# Faders.net
KiCad netlist of a schematic drawn in EAGLE
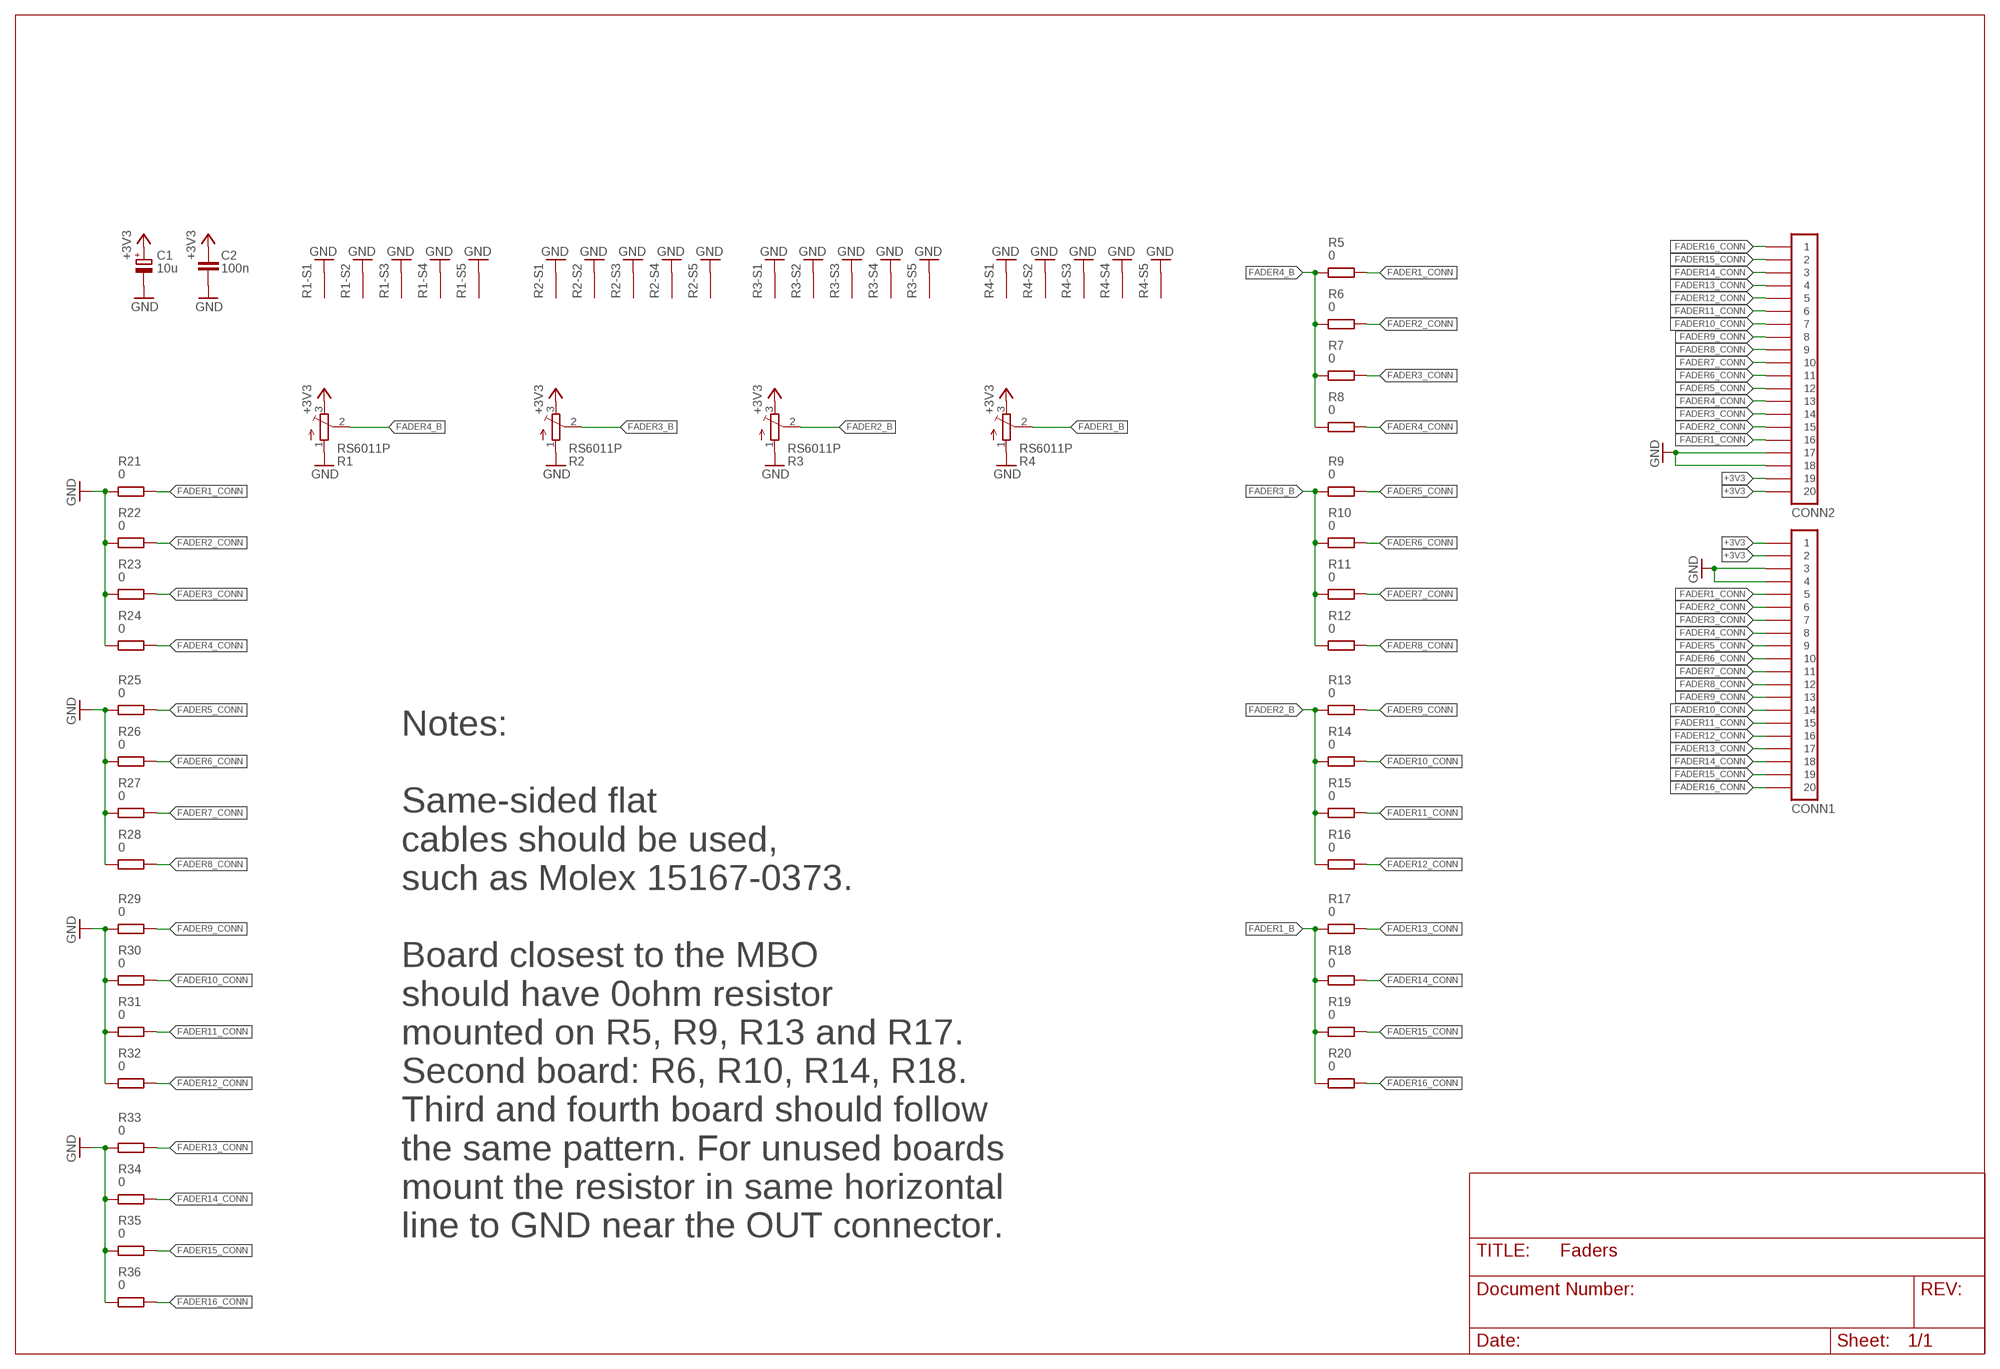
[diagram p0: schematic, sheet 1]

(export (version "E")
  (design (tool "Eeschema 10.0.6"))
  (components
    (comp (ref "C1")
      (value "10u")
      (footprint "eagle-import:C-TH-E-0401")
      (libsource (lib "eagle-import") (part "ELECTROLYTIC_CAPACITOR-C-TH-E-0401"))
    )
    (comp (ref "C2")
      (value "100n")
      (footprint "eagle-import:C0805")
      (libsource (lib "eagle-import") (part "CAPACITOR-0805"))
    )
    (comp (ref "CONN1")
      (value "PINHD-1X20-SMD")
      (footprint "eagle-import:MOLEX-52271-2079")
      (fields (field (name "MANUFACTURER") "Molex") (field (name "MPN") "52271-2079"))
      (libsource (lib "eagle-import") (part "PINHD-1X20-SMD"))
    )
    (comp (ref "CONN2")
      (value "PINHD-1X20-SMD")
      (footprint "eagle-import:MOLEX-52271-2079")
      (fields (field (name "MANUFACTURER") "Molex") (field (name "MPN") "52271-2079"))
      (libsource (lib "eagle-import") (part "PINHD-1X20-SMD"))
    )
    (comp (ref "R1")
      (value "RS6011P")
      (footprint "eagle-import:RS6011_P")
      (libsource (lib "eagle-import") (part "RS6011P"))
    )
    (comp (ref "R2")
      (value "RS6011P")
      (footprint "eagle-import:RS6011_P")
      (libsource (lib "eagle-import") (part "RS6011P"))
    )
    (comp (ref "R3")
      (value "RS6011P")
      (footprint "eagle-import:RS6011_P")
      (libsource (lib "eagle-import") (part "RS6011P"))
    )
    (comp (ref "R4")
      (value "RS6011P")
      (footprint "eagle-import:RS6011_P")
      (libsource (lib "eagle-import") (part "RS6011P"))
    )
    (comp (ref "R5")
      (value "0")
      (footprint "eagle-import:R0805")
      (libsource (lib "eagle-import") (part "RESISTOR-0805"))
    )
    (comp (ref "R6")
      (value "0")
      (footprint "eagle-import:R0805")
      (libsource (lib "eagle-import") (part "RESISTOR-0805"))
    )
    (comp (ref "R7")
      (value "0")
      (footprint "eagle-import:R0805")
      (libsource (lib "eagle-import") (part "RESISTOR-0805"))
    )
    (comp (ref "R8")
      (value "0")
      (footprint "eagle-import:R0805")
      (libsource (lib "eagle-import") (part "RESISTOR-0805"))
    )
    (comp (ref "R9")
      (value "0")
      (footprint "eagle-import:R0805")
      (libsource (lib "eagle-import") (part "RESISTOR-0805"))
    )
    (comp (ref "R10")
      (value "0")
      (footprint "eagle-import:R0805")
      (libsource (lib "eagle-import") (part "RESISTOR-0805"))
    )
    (comp (ref "R11")
      (value "0")
      (footprint "eagle-import:R0805")
      (libsource (lib "eagle-import") (part "RESISTOR-0805"))
    )
    (comp (ref "R12")
      (value "0")
      (footprint "eagle-import:R0805")
      (libsource (lib "eagle-import") (part "RESISTOR-0805"))
    )
    (comp (ref "R13")
      (value "0")
      (footprint "eagle-import:R0805")
      (libsource (lib "eagle-import") (part "RESISTOR-0805"))
    )
    (comp (ref "R14")
      (value "0")
      (footprint "eagle-import:R0805")
      (libsource (lib "eagle-import") (part "RESISTOR-0805"))
    )
    (comp (ref "R15")
      (value "0")
      (footprint "eagle-import:R0805")
      (libsource (lib "eagle-import") (part "RESISTOR-0805"))
    )
    (comp (ref "R16")
      (value "0")
      (footprint "eagle-import:R0805")
      (libsource (lib "eagle-import") (part "RESISTOR-0805"))
    )
    (comp (ref "R17")
      (value "0")
      (footprint "eagle-import:R0805")
      (libsource (lib "eagle-import") (part "RESISTOR-0805"))
    )
    (comp (ref "R18")
      (value "0")
      (footprint "eagle-import:R0805")
      (libsource (lib "eagle-import") (part "RESISTOR-0805"))
    )
    (comp (ref "R19")
      (value "0")
      (footprint "eagle-import:R0805")
      (libsource (lib "eagle-import") (part "RESISTOR-0805"))
    )
    (comp (ref "R20")
      (value "0")
      (footprint "eagle-import:R0805")
      (libsource (lib "eagle-import") (part "RESISTOR-0805"))
    )
    (comp (ref "R21")
      (value "0")
      (footprint "eagle-import:R0805")
      (libsource (lib "eagle-import") (part "RESISTOR-0805"))
    )
    (comp (ref "R22")
      (value "0")
      (footprint "eagle-import:R0805")
      (libsource (lib "eagle-import") (part "RESISTOR-0805"))
    )
    (comp (ref "R23")
      (value "0")
      (footprint "eagle-import:R0805")
      (libsource (lib "eagle-import") (part "RESISTOR-0805"))
    )
    (comp (ref "R24")
      (value "0")
      (footprint "eagle-import:R0805")
      (libsource (lib "eagle-import") (part "RESISTOR-0805"))
    )
    (comp (ref "R25")
      (value "0")
      (footprint "eagle-import:R0805")
      (libsource (lib "eagle-import") (part "RESISTOR-0805"))
    )
    (comp (ref "R26")
      (value "0")
      (footprint "eagle-import:R0805")
      (libsource (lib "eagle-import") (part "RESISTOR-0805"))
    )
    (comp (ref "R27")
      (value "0")
      (footprint "eagle-import:R0805")
      (libsource (lib "eagle-import") (part "RESISTOR-0805"))
    )
    (comp (ref "R28")
      (value "0")
      (footprint "eagle-import:R0805")
      (libsource (lib "eagle-import") (part "RESISTOR-0805"))
    )
    (comp (ref "R29")
      (value "0")
      (footprint "eagle-import:R0805")
      (libsource (lib "eagle-import") (part "RESISTOR-0805"))
    )
    (comp (ref "R30")
      (value "0")
      (footprint "eagle-import:R0805")
      (libsource (lib "eagle-import") (part "RESISTOR-0805"))
    )
    (comp (ref "R31")
      (value "0")
      (footprint "eagle-import:R0805")
      (libsource (lib "eagle-import") (part "RESISTOR-0805"))
    )
    (comp (ref "R32")
      (value "0")
      (footprint "eagle-import:R0805")
      (libsource (lib "eagle-import") (part "RESISTOR-0805"))
    )
    (comp (ref "R33")
      (value "0")
      (footprint "eagle-import:R0805")
      (libsource (lib "eagle-import") (part "RESISTOR-0805"))
    )
    (comp (ref "R34")
      (value "0")
      (footprint "eagle-import:R0805")
      (libsource (lib "eagle-import") (part "RESISTOR-0805"))
    )
    (comp (ref "R35")
      (value "0")
      (footprint "eagle-import:R0805")
      (libsource (lib "eagle-import") (part "RESISTOR-0805"))
    )
    (comp (ref "R36")
      (value "0")
      (footprint "eagle-import:R0805")
      (libsource (lib "eagle-import") (part "RESISTOR-0805"))
    )
  )
  (nets
    (net (code "1") (name "+3V3") (class "Default")
      (node (ref "C1") (pin "+") (pinfunction "+_+") (pintype "passive"))
      (node (ref "C2") (pin "1") (pinfunction "1_1") (pintype "passive"))
      (node (ref "CONN1") (pin "1") (pinfunction "1_1") (pintype "passive"))
      (node (ref "CONN1") (pin "2") (pinfunction "2_2") (pintype "passive"))
      (node (ref "CONN2") (pin "19") (pinfunction "19_19") (pintype "passive"))
      (node (ref "CONN2") (pin "20") (pinfunction "20_20") (pintype "passive"))
      (node (ref "R1") (pin "3") (pinfunction "3_3") (pintype "passive"))
      (node (ref "R2") (pin "3") (pinfunction "3_3") (pintype "passive"))
      (node (ref "R3") (pin "3") (pinfunction "3_3") (pintype "passive"))
      (node (ref "R4") (pin "3") (pinfunction "3_3") (pintype "passive"))
    )
    (net (code "2") (name "FADER1_B") (class "Default")
      (node (ref "R17") (pin "1") (pinfunction "1_1") (pintype "passive"))
      (node (ref "R18") (pin "1") (pinfunction "1_1") (pintype "passive"))
      (node (ref "R19") (pin "1") (pinfunction "1_1") (pintype "passive"))
      (node (ref "R20") (pin "1") (pinfunction "1_1") (pintype "passive"))
      (node (ref "R4") (pin "2") (pinfunction "2_2") (pintype "passive"))
    )
    (net (code "3") (name "FADER1_CONN") (class "Default")
      (node (ref "CONN1") (pin "5") (pinfunction "5_5") (pintype "passive"))
      (node (ref "CONN2") (pin "16") (pinfunction "16_16") (pintype "passive"))
      (node (ref "R21") (pin "2") (pinfunction "2_2") (pintype "passive"))
      (node (ref "R5") (pin "2") (pinfunction "2_2") (pintype "passive"))
    )
    (net (code "4") (name "FADER2_B") (class "Default")
      (node (ref "R13") (pin "1") (pinfunction "1_1") (pintype "passive"))
      (node (ref "R14") (pin "1") (pinfunction "1_1") (pintype "passive"))
      (node (ref "R15") (pin "1") (pinfunction "1_1") (pintype "passive"))
      (node (ref "R16") (pin "1") (pinfunction "1_1") (pintype "passive"))
      (node (ref "R3") (pin "2") (pinfunction "2_2") (pintype "passive"))
    )
    (net (code "5") (name "FADER2_CONN") (class "Default")
      (node (ref "CONN1") (pin "6") (pinfunction "6_6") (pintype "passive"))
      (node (ref "CONN2") (pin "15") (pinfunction "15_15") (pintype "passive"))
      (node (ref "R22") (pin "2") (pinfunction "2_2") (pintype "passive"))
      (node (ref "R6") (pin "2") (pinfunction "2_2") (pintype "passive"))
    )
    (net (code "6") (name "FADER3_B") (class "Default")
      (node (ref "R10") (pin "1") (pinfunction "1_1") (pintype "passive"))
      (node (ref "R11") (pin "1") (pinfunction "1_1") (pintype "passive"))
      (node (ref "R12") (pin "1") (pinfunction "1_1") (pintype "passive"))
      (node (ref "R2") (pin "2") (pinfunction "2_2") (pintype "passive"))
      (node (ref "R9") (pin "1") (pinfunction "1_1") (pintype "passive"))
    )
    (net (code "7") (name "FADER3_CONN") (class "Default")
      (node (ref "CONN1") (pin "7") (pinfunction "7_7") (pintype "passive"))
      (node (ref "CONN2") (pin "14") (pinfunction "14_14") (pintype "passive"))
      (node (ref "R23") (pin "2") (pinfunction "2_2") (pintype "passive"))
      (node (ref "R7") (pin "2") (pinfunction "2_2") (pintype "passive"))
    )
    (net (code "8") (name "FADER4_B") (class "Default")
      (node (ref "R1") (pin "2") (pinfunction "2_2") (pintype "passive"))
      (node (ref "R5") (pin "1") (pinfunction "1_1") (pintype "passive"))
      (node (ref "R6") (pin "1") (pinfunction "1_1") (pintype "passive"))
      (node (ref "R7") (pin "1") (pinfunction "1_1") (pintype "passive"))
      (node (ref "R8") (pin "1") (pinfunction "1_1") (pintype "passive"))
    )
    (net (code "9") (name "FADER4_CONN") (class "Default")
      (node (ref "CONN1") (pin "8") (pinfunction "8_8") (pintype "passive"))
      (node (ref "CONN2") (pin "13") (pinfunction "13_13") (pintype "passive"))
      (node (ref "R24") (pin "2") (pinfunction "2_2") (pintype "passive"))
      (node (ref "R8") (pin "2") (pinfunction "2_2") (pintype "passive"))
    )
    (net (code "10") (name "FADER5_CONN") (class "Default")
      (node (ref "CONN1") (pin "9") (pinfunction "9_9") (pintype "passive"))
      (node (ref "CONN2") (pin "12") (pinfunction "12_12") (pintype "passive"))
      (node (ref "R25") (pin "2") (pinfunction "2_2") (pintype "passive"))
      (node (ref "R9") (pin "2") (pinfunction "2_2") (pintype "passive"))
    )
    (net (code "11") (name "FADER6_CONN") (class "Default")
      (node (ref "CONN1") (pin "10") (pinfunction "10_10") (pintype "passive"))
      (node (ref "CONN2") (pin "11") (pinfunction "11_11") (pintype "passive"))
      (node (ref "R10") (pin "2") (pinfunction "2_2") (pintype "passive"))
      (node (ref "R26") (pin "2") (pinfunction "2_2") (pintype "passive"))
    )
    (net (code "12") (name "FADER7_CONN") (class "Default")
      (node (ref "CONN1") (pin "11") (pinfunction "11_11") (pintype "passive"))
      (node (ref "CONN2") (pin "10") (pinfunction "10_10") (pintype "passive"))
      (node (ref "R11") (pin "2") (pinfunction "2_2") (pintype "passive"))
      (node (ref "R27") (pin "2") (pinfunction "2_2") (pintype "passive"))
    )
    (net (code "13") (name "FADER8_CONN") (class "Default")
      (node (ref "CONN1") (pin "12") (pinfunction "12_12") (pintype "passive"))
      (node (ref "CONN2") (pin "9") (pinfunction "9_9") (pintype "passive"))
      (node (ref "R12") (pin "2") (pinfunction "2_2") (pintype "passive"))
      (node (ref "R28") (pin "2") (pinfunction "2_2") (pintype "passive"))
    )
    (net (code "14") (name "FADER9_CONN") (class "Default")
      (node (ref "CONN1") (pin "13") (pinfunction "13_13") (pintype "passive"))
      (node (ref "CONN2") (pin "8") (pinfunction "8_8") (pintype "passive"))
      (node (ref "R13") (pin "2") (pinfunction "2_2") (pintype "passive"))
      (node (ref "R29") (pin "2") (pinfunction "2_2") (pintype "passive"))
    )
    (net (code "15") (name "FADER10_CONN") (class "Default")
      (node (ref "CONN1") (pin "14") (pinfunction "14_14") (pintype "passive"))
      (node (ref "CONN2") (pin "7") (pinfunction "7_7") (pintype "passive"))
      (node (ref "R14") (pin "2") (pinfunction "2_2") (pintype "passive"))
      (node (ref "R30") (pin "2") (pinfunction "2_2") (pintype "passive"))
    )
    (net (code "16") (name "FADER11_CONN") (class "Default")
      (node (ref "CONN1") (pin "15") (pinfunction "15_15") (pintype "passive"))
      (node (ref "CONN2") (pin "6") (pinfunction "6_6") (pintype "passive"))
      (node (ref "R15") (pin "2") (pinfunction "2_2") (pintype "passive"))
      (node (ref "R31") (pin "2") (pinfunction "2_2") (pintype "passive"))
    )
    (net (code "17") (name "FADER12_CONN") (class "Default")
      (node (ref "CONN1") (pin "16") (pinfunction "16_16") (pintype "passive"))
      (node (ref "CONN2") (pin "5") (pinfunction "5_5") (pintype "passive"))
      (node (ref "R16") (pin "2") (pinfunction "2_2") (pintype "passive"))
      (node (ref "R32") (pin "2") (pinfunction "2_2") (pintype "passive"))
    )
    (net (code "18") (name "FADER13_CONN") (class "Default")
      (node (ref "CONN1") (pin "17") (pinfunction "17_17") (pintype "passive"))
      (node (ref "CONN2") (pin "4") (pinfunction "4_4") (pintype "passive"))
      (node (ref "R17") (pin "2") (pinfunction "2_2") (pintype "passive"))
      (node (ref "R33") (pin "2") (pinfunction "2_2") (pintype "passive"))
    )
    (net (code "19") (name "FADER14_CONN") (class "Default")
      (node (ref "CONN1") (pin "18") (pinfunction "18_18") (pintype "passive"))
      (node (ref "CONN2") (pin "3") (pinfunction "3_3") (pintype "passive"))
      (node (ref "R18") (pin "2") (pinfunction "2_2") (pintype "passive"))
      (node (ref "R34") (pin "2") (pinfunction "2_2") (pintype "passive"))
    )
    (net (code "20") (name "FADER15_CONN") (class "Default")
      (node (ref "CONN1") (pin "19") (pinfunction "19_19") (pintype "passive"))
      (node (ref "CONN2") (pin "2") (pinfunction "2_2") (pintype "passive"))
      (node (ref "R19") (pin "2") (pinfunction "2_2") (pintype "passive"))
      (node (ref "R35") (pin "2") (pinfunction "2_2") (pintype "passive"))
    )
    (net (code "21") (name "FADER16_CONN") (class "Default")
      (node (ref "CONN1") (pin "20") (pinfunction "20_20") (pintype "passive"))
      (node (ref "CONN2") (pin "1") (pinfunction "1_1") (pintype "passive"))
      (node (ref "R20") (pin "2") (pinfunction "2_2") (pintype "passive"))
      (node (ref "R36") (pin "2") (pinfunction "2_2") (pintype "passive"))
    )
    (net (code "22") (name "GND") (class "Default")
      (node (ref "C1") (pin "-") (pinfunction "-_-") (pintype "passive"))
      (node (ref "C2") (pin "2") (pinfunction "2_2") (pintype "passive"))
      (node (ref "CONN1") (pin "3") (pinfunction "3_3") (pintype "passive"))
      (node (ref "CONN1") (pin "4") (pinfunction "4_4") (pintype "passive"))
      (node (ref "CONN2") (pin "17") (pinfunction "17_17") (pintype "passive"))
      (node (ref "CONN2") (pin "18") (pinfunction "18_18") (pintype "passive"))
      (node (ref "R1") (pin "1") (pinfunction "1_1") (pintype "passive"))
      (node (ref "R1") (pin "S1") (pinfunction "S_S1") (pintype "passive"))
      (node (ref "R1") (pin "S2") (pinfunction "S_S2") (pintype "passive"))
      (node (ref "R1") (pin "S3") (pinfunction "S_S3") (pintype "passive"))
      (node (ref "R1") (pin "S4") (pinfunction "S_S4") (pintype "passive"))
      (node (ref "R1") (pin "S5") (pinfunction "S_S5") (pintype "passive"))
      (node (ref "R2") (pin "1") (pinfunction "1_1") (pintype "passive"))
      (node (ref "R2") (pin "S1") (pinfunction "S_S1") (pintype "passive"))
      (node (ref "R2") (pin "S2") (pinfunction "S_S2") (pintype "passive"))
      (node (ref "R2") (pin "S3") (pinfunction "S_S3") (pintype "passive"))
      (node (ref "R2") (pin "S4") (pinfunction "S_S4") (pintype "passive"))
      (node (ref "R2") (pin "S5") (pinfunction "S_S5") (pintype "passive"))
      (node (ref "R21") (pin "1") (pinfunction "1_1") (pintype "passive"))
      (node (ref "R22") (pin "1") (pinfunction "1_1") (pintype "passive"))
      (node (ref "R23") (pin "1") (pinfunction "1_1") (pintype "passive"))
      (node (ref "R24") (pin "1") (pinfunction "1_1") (pintype "passive"))
      (node (ref "R25") (pin "1") (pinfunction "1_1") (pintype "passive"))
      (node (ref "R26") (pin "1") (pinfunction "1_1") (pintype "passive"))
      (node (ref "R27") (pin "1") (pinfunction "1_1") (pintype "passive"))
      (node (ref "R28") (pin "1") (pinfunction "1_1") (pintype "passive"))
      (node (ref "R29") (pin "1") (pinfunction "1_1") (pintype "passive"))
      (node (ref "R3") (pin "1") (pinfunction "1_1") (pintype "passive"))
      (node (ref "R3") (pin "S1") (pinfunction "S_S1") (pintype "passive"))
      (node (ref "R3") (pin "S2") (pinfunction "S_S2") (pintype "passive"))
      (node (ref "R3") (pin "S3") (pinfunction "S_S3") (pintype "passive"))
      (node (ref "R3") (pin "S4") (pinfunction "S_S4") (pintype "passive"))
      (node (ref "R3") (pin "S5") (pinfunction "S_S5") (pintype "passive"))
      (node (ref "R30") (pin "1") (pinfunction "1_1") (pintype "passive"))
      (node (ref "R31") (pin "1") (pinfunction "1_1") (pintype "passive"))
      (node (ref "R32") (pin "1") (pinfunction "1_1") (pintype "passive"))
      (node (ref "R33") (pin "1") (pinfunction "1_1") (pintype "passive"))
      (node (ref "R34") (pin "1") (pinfunction "1_1") (pintype "passive"))
      (node (ref "R35") (pin "1") (pinfunction "1_1") (pintype "passive"))
      (node (ref "R36") (pin "1") (pinfunction "1_1") (pintype "passive"))
      (node (ref "R4") (pin "1") (pinfunction "1_1") (pintype "passive"))
      (node (ref "R4") (pin "S1") (pinfunction "S_S1") (pintype "passive"))
      (node (ref "R4") (pin "S2") (pinfunction "S_S2") (pintype "passive"))
      (node (ref "R4") (pin "S3") (pinfunction "S_S3") (pintype "passive"))
      (node (ref "R4") (pin "S4") (pinfunction "S_S4") (pintype "passive"))
      (node (ref "R4") (pin "S5") (pinfunction "S_S5") (pintype "passive"))
    )
  )
)
